# PRECISION_CLOCK_1.net
KiCad netlist of a schematic drawn in EAGLE
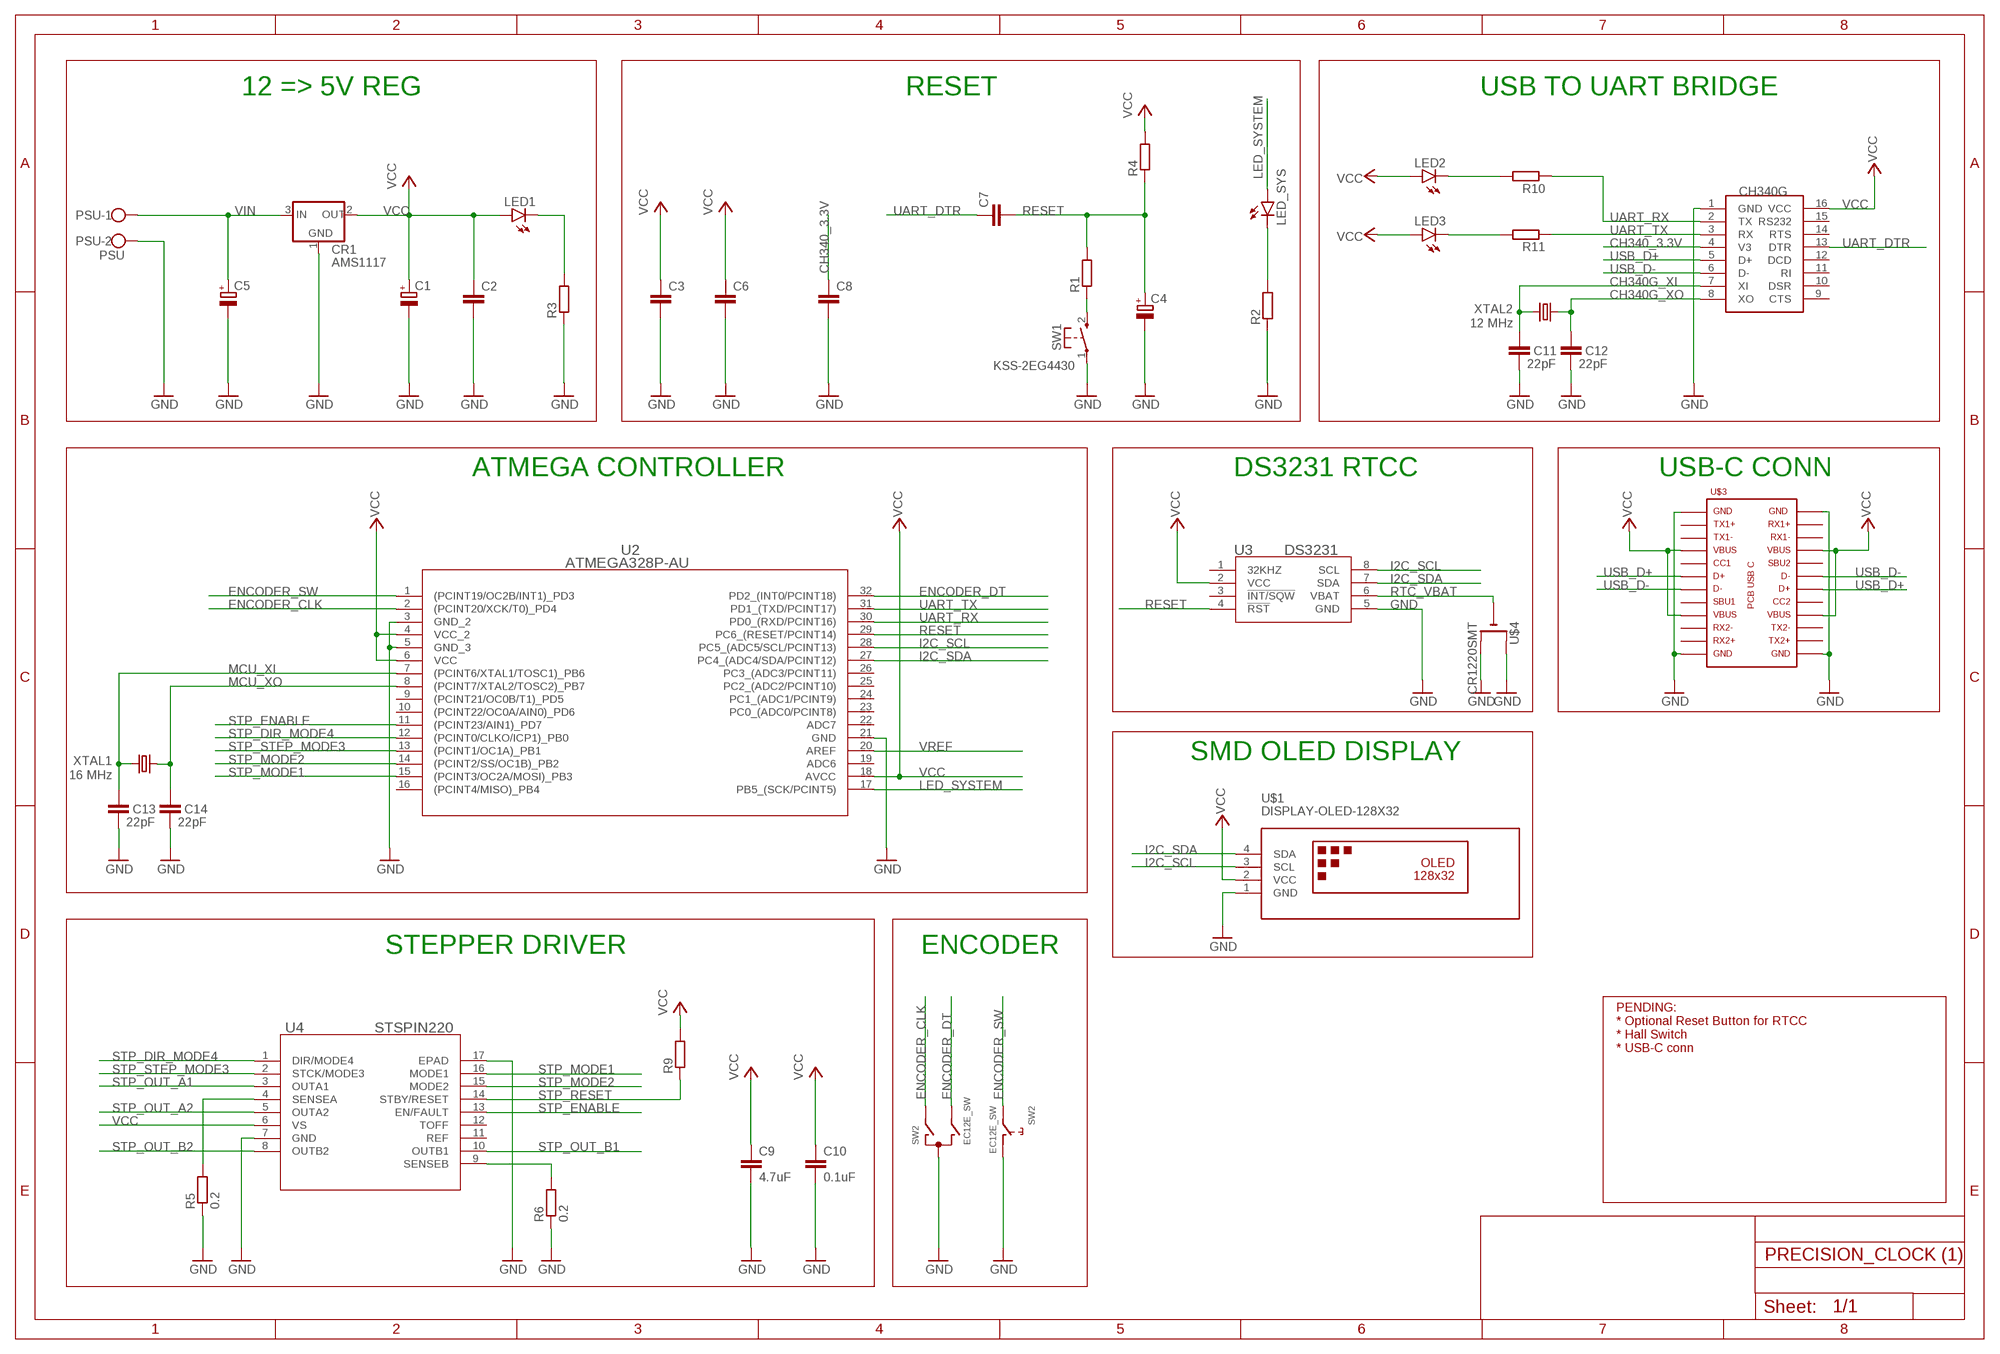
[diagram p0: schematic, sheet 1]

(export (version "E")
  (design (tool "Eeschema 10.0.6"))
  (components
    (comp (ref "C1")
      (value "CPOL-EU153CLV-0505")
      (footprint "eagle-import:153CLV-0505")
      (libsource (lib "eagle-import") (part "CPOL-EU153CLV-0505"))
    )
    (comp (ref "C2")
      (value "C-EUC0805")
      (footprint "eagle-import:C0805")
      (libsource (lib "eagle-import") (part "C-EUC0805"))
    )
    (comp (ref "C3")
      (value "C-EUC0805")
      (footprint "eagle-import:C0805")
      (libsource (lib "eagle-import") (part "C-EUC0805"))
    )
    (comp (ref "C4")
      (value "CPOL-EU153CLV-0505")
      (footprint "eagle-import:153CLV-0505")
      (libsource (lib "eagle-import") (part "CPOL-EU153CLV-0505"))
    )
    (comp (ref "C5")
      (value "CPOL-EU153CLV-0505")
      (footprint "eagle-import:153CLV-0505")
      (libsource (lib "eagle-import") (part "CPOL-EU153CLV-0505"))
    )
    (comp (ref "C6")
      (value "C-EUC0805")
      (footprint "eagle-import:C0805")
      (libsource (lib "eagle-import") (part "C-EUC0805"))
    )
    (comp (ref "C7")
      (value "C-EUC0805")
      (footprint "eagle-import:C0805")
      (libsource (lib "eagle-import") (part "C-EUC0805"))
    )
    (comp (ref "C8")
      (value "C-EUC0805")
      (footprint "eagle-import:C0805")
      (libsource (lib "eagle-import") (part "C-EUC0805"))
    )
    (comp (ref "C9")
      (value "4.7uF")
      (footprint "eagle-import:C0805")
      (libsource (lib "eagle-import") (part "C-EUC0805"))
    )
    (comp (ref "C10")
      (value "0.1uF")
      (footprint "eagle-import:C0805")
      (libsource (lib "eagle-import") (part "C-EUC0805"))
    )
    (comp (ref "C11")
      (value "22pF")
      (footprint "eagle-import:C0805")
      (libsource (lib "eagle-import") (part "C-EUC0805"))
    )
    (comp (ref "C12")
      (value "22pF")
      (footprint "eagle-import:C0805")
      (libsource (lib "eagle-import") (part "C-EUC0805"))
    )
    (comp (ref "C13")
      (value "22pF")
      (footprint "eagle-import:C0805")
      (libsource (lib "eagle-import") (part "C-EUC0805"))
    )
    (comp (ref "C14")
      (value "22pF")
      (footprint "eagle-import:C0805")
      (libsource (lib "eagle-import") (part "C-EUC0805"))
    )
    (comp (ref "CR1")
      (value "AMS1117")
      (footprint "eagle-import:SOT223")
      (libsource (lib "eagle-import") (part "AMS1117"))
    )
    (comp (ref "LED1")
      (value "LEDSML0805")
      (footprint "eagle-import:SML0805")
      (libsource (lib "eagle-import") (part "LEDSML0805"))
    )
    (comp (ref "LED2")
      (value "LEDSML0805")
      (footprint "eagle-import:SML0805")
      (libsource (lib "eagle-import") (part "LEDSML0805"))
    )
    (comp (ref "LED3")
      (value "LEDSML0805")
      (footprint "eagle-import:SML0805")
      (libsource (lib "eagle-import") (part "LEDSML0805"))
    )
    (comp (ref "LED_SYS")
      (value "LEDSML0805")
      (footprint "eagle-import:SML0805")
      (libsource (lib "eagle-import") (part "LEDSML0805"))
    )
    (comp (ref "PSU")
      (value "PSU")
      (footprint "eagle-import:W237-102")
      (fields (field (name "MPN") "237-102"))
      (libsource (lib "eagle-import") (part "W237-102"))
    )
    (comp (ref "R1")
      (value "R-EU_R0805")
      (footprint "eagle-import:R0805")
      (libsource (lib "eagle-import") (part "R-EU_R0805"))
    )
    (comp (ref "R2")
      (value "R-EU_R0805")
      (footprint "eagle-import:R0805")
      (libsource (lib "eagle-import") (part "R-EU_R0805"))
    )
    (comp (ref "R3")
      (value "R-EU_R0805")
      (footprint "eagle-import:R0805")
      (libsource (lib "eagle-import") (part "R-EU_R0805"))
    )
    (comp (ref "R4")
      (value "R-EU_R0805")
      (footprint "eagle-import:R0805")
      (libsource (lib "eagle-import") (part "R-EU_R0805"))
    )
    (comp (ref "R5")
      (value "0.2")
      (footprint "eagle-import:R0805")
      (libsource (lib "eagle-import") (part "R-EU_R0805"))
    )
    (comp (ref "R6")
      (value "0.2")
      (footprint "eagle-import:R0805")
      (libsource (lib "eagle-import") (part "R-EU_R0805"))
    )
    (comp (ref "R9")
      (value "R-EU_R0805")
      (footprint "eagle-import:R0805")
      (libsource (lib "eagle-import") (part "R-EU_R0805"))
    )
    (comp (ref "R10")
      (value "R-EU_R0805")
      (footprint "eagle-import:R0805")
      (libsource (lib "eagle-import") (part "R-EU_R0805"))
    )
    (comp (ref "R11")
      (value "R-EU_R0805")
      (footprint "eagle-import:R0805")
      (libsource (lib "eagle-import") (part "R-EU_R0805"))
    )
    (comp (ref "SW1")
      (value "KSS-2EG4430")
      (footprint "eagle-import:KSS-2EG4430")
      (libsource (lib "eagle-import") (part "KSS-2EG4430"))
    )
    (comp (ref "SW2")
      (value "EC12E_SW")
      (footprint "eagle-import:ALPS_EC12E_SW")
      (fields (field (name "MPN") "EC12E2424407"))
      (libsource (lib "eagle-import") (part "EC12E_SW"))
    )
    (comp (ref "U$1")
      (value "DISPLAY-OLED-128X32")
      (footprint "eagle-import:DISPLAY-OLED-128X32")
      (libsource (lib "eagle-import") (part "DISPLAY-OLED-128X32"))
    )
    (comp (ref "U$2")
      (value "CH340G")
      (footprint "eagle-import:SOIC16")
      (libsource (lib "eagle-import") (part "CH340G"))
    )
    (comp (ref "U$3")
      (value "PCB_USB_CDS_2")
      (footprint "eagle-import:USB_TYPE_C_DS_2")
      (libsource (lib "eagle-import") (part "PCB_USB_CDS_2"))
    )
    (comp (ref "U$4")
      (value "CR1220SMT")
      (footprint "eagle-import:CR1220-SMD")
      (fields (field (name "MF") "FDK America, Inc., a member of Fujitsu Group") (field (name "MP") "CR1220"))
      (libsource (lib "eagle-import") (part "CR1220SMT"))
    )
    (comp (ref "U2")
      (value "ATMEGA328P-AU")
      (footprint "eagle-import:32A_ATM")
      (libsource (lib "eagle-import") (part "ATMEGA328P-AU"))
    )
    (comp (ref "U3")
      (value "DS3231")
      (footprint "eagle-import:21-0041B_8_MXM")
      (fields (field (name "MANUFACTURER_PART_NUMBER") "DS3231MZ/V+T"))
      (libsource (lib "eagle-import") (part "DS3231"))
    )
    (comp (ref "U4")
      (value "STSPIN220")
      (footprint "eagle-import:VFQFPN-16_STM")
      (fields (field (name "COPYRIGHT") "Copyright (C) 2018 Accelerated Designs. All rights reserved"))
      (libsource (lib "eagle-import") (part "STSPIN220"))
    )
    (comp (ref "XTAL1")
      (value "16 MHz")
      (footprint "eagle-import:SM49")
      (libsource (lib "eagle-import") (part "CRYSTALSM49"))
    )
    (comp (ref "XTAL2")
      (value "12 MHz")
      (footprint "eagle-import:SM49")
      (libsource (lib "eagle-import") (part "CRYSTALSM49"))
    )
  )
  (nets
    (net (code "1") (name "/CH340G_XI") (class "Default")
      (node (ref "C11") (pin "1") (pinfunction "1_1") (pintype "passive"))
      (node (ref "U$2") (pin "7") (pinfunction "XI_7") (pintype "bidirectional"))
      (node (ref "XTAL2") (pin "2") (pinfunction "2_2") (pintype "passive"))
    )
    (net (code "2") (name "/CH340G_XO") (class "Default")
      (node (ref "C12") (pin "1") (pinfunction "1_1") (pintype "passive"))
      (node (ref "U$2") (pin "8") (pinfunction "XO_8") (pintype "bidirectional"))
      (node (ref "XTAL2") (pin "1") (pinfunction "1_1") (pintype "passive"))
    )
    (net (code "3") (name "/CH340_3.3V") (class "Default")
      (node (ref "C8") (pin "1") (pinfunction "1_1") (pintype "passive"))
      (node (ref "U$2") (pin "4") (pinfunction "V3_4") (pintype "bidirectional"))
    )
    (net (code "4") (name "/ENCODER_CLK") (class "Default")
      (node (ref "SW2") (pin "A") (pinfunction "A_A") (pintype "passive"))
      (node (ref "U2") (pin "2") (pinfunction "(PCINT20/XCK/T0)_PD4_2") (pintype "bidirectional"))
    )
    (net (code "5") (name "/ENCODER_DT") (class "Default")
      (node (ref "SW2") (pin "B") (pinfunction "B_B") (pintype "passive"))
      (node (ref "U2") (pin "32") (pinfunction "PD2_(INT0/PCINT18)_32") (pintype "bidirectional"))
    )
    (net (code "6") (name "/ENCODER_SW") (class "Default")
      (node (ref "SW2") (pin "E") (pinfunction "2_E") (pintype "passive"))
      (node (ref "U2") (pin "1") (pinfunction "(PCINT19/OC2B/INT1)_PD3_1") (pintype "bidirectional"))
    )
    (net (code "7") (name "/I2C_SCL") (class "Default")
      (node (ref "U$1") (pin "3") (pinfunction "SCL_3") (pintype "bidirectional"))
      (node (ref "U2") (pin "28") (pinfunction "PC5_(ADC5/SCL/PCINT13)_28") (pintype "bidirectional"))
      (node (ref "U3") (pin "8") (pinfunction "SCL_8") (pintype "passive"))
    )
    (net (code "8") (name "/I2C_SDA") (class "Default")
      (node (ref "U$1") (pin "4") (pinfunction "SDA_4") (pintype "bidirectional"))
      (node (ref "U2") (pin "27") (pinfunction "PC4_(ADC4/SDA/PCINT12)_27") (pintype "bidirectional"))
      (node (ref "U3") (pin "7") (pinfunction "SDA_7") (pintype "passive"))
    )
    (net (code "9") (name "/LED_SYSTEM") (class "Default")
      (node (ref "LED_SYS") (pin "A") (pinfunction "A_A") (pintype "passive"))
      (node (ref "U2") (pin "17") (pinfunction "PB5_(SCK/PCINT5)_17") (pintype "bidirectional"))
    )
    (net (code "10") (name "/MCU_XI") (class "Default")
      (node (ref "C13") (pin "1") (pinfunction "1_1") (pintype "passive"))
      (node (ref "U2") (pin "7") (pinfunction "(PCINT6/XTAL1/TOSC1)_PB6_7") (pintype "bidirectional"))
      (node (ref "XTAL1") (pin "2") (pinfunction "2_2") (pintype "passive"))
    )
    (net (code "11") (name "/MCU_XO") (class "Default")
      (node (ref "C14") (pin "1") (pinfunction "1_1") (pintype "passive"))
      (node (ref "U2") (pin "8") (pinfunction "(PCINT7/XTAL2/TOSC2)_PB7_8") (pintype "bidirectional"))
      (node (ref "XTAL1") (pin "1") (pinfunction "1_1") (pintype "passive"))
    )
    (net (code "12") (name "/RESET") (class "Default")
      (node (ref "C4") (pin "+") (pinfunction "+_+") (pintype "passive"))
      (node (ref "C7") (pin "2") (pinfunction "2_2") (pintype "passive"))
      (node (ref "R1") (pin "2") (pinfunction "2_2") (pintype "passive"))
      (node (ref "R4") (pin "1") (pinfunction "1_1") (pintype "passive"))
      (node (ref "U2") (pin "29") (pinfunction "PC6_(RESET/PCINT14)_29") (pintype "bidirectional"))
      (node (ref "U3") (pin "4") (pinfunction "~{RST}_4") (pintype "passive"))
    )
    (net (code "13") (name "/RTC_VBAT") (class "Default")
      (node (ref "U$4") (pin "-") (pinfunction "-_-") (pintype "passive"))
      (node (ref "U3") (pin "6") (pinfunction "VBAT_6") (pintype "power_in"))
    )
    (net (code "14") (name "/STP_DIR_MODE4") (class "Default")
      (node (ref "U2") (pin "12") (pinfunction "(PCINT0/CLKO/ICP1)_PB0_12") (pintype "bidirectional"))
      (node (ref "U4") (pin "1") (pinfunction "DIR/MODE4_1") (pintype "input"))
    )
    (net (code "15") (name "/STP_ENABLE") (class "Default")
      (node (ref "U2") (pin "11") (pinfunction "(PCINT23/AIN1)_PD7_11") (pintype "bidirectional"))
      (node (ref "U4") (pin "13") (pinfunction "EN/FAULT_13") (pintype "bidirectional"))
    )
    (net (code "16") (name "/STP_MODE1") (class "Default")
      (node (ref "U2") (pin "15") (pinfunction "(PCINT3/OC2A/MOSI)_PB3_15") (pintype "bidirectional"))
      (node (ref "U4") (pin "16") (pinfunction "MODE1_16") (pintype "input"))
    )
    (net (code "17") (name "/STP_MODE2") (class "Default")
      (node (ref "U2") (pin "14") (pinfunction "(PCINT2/SS/OC1B)_PB2_14") (pintype "bidirectional"))
      (node (ref "U4") (pin "15") (pinfunction "MODE2_15") (pintype "input"))
    )
    (net (code "18") (name "/STP_OUT_A1") (class "Default")
      (node (ref "U4") (pin "3") (pinfunction "OUTA1_3") (pintype "output"))
    )
    (net (code "19") (name "/STP_OUT_A2") (class "Default")
      (node (ref "U4") (pin "5") (pinfunction "OUTA2_5") (pintype "output"))
    )
    (net (code "20") (name "/STP_OUT_B1") (class "Default")
      (node (ref "U4") (pin "10") (pinfunction "OUTB1_10") (pintype "output"))
    )
    (net (code "21") (name "/STP_OUT_B2") (class "Default")
      (node (ref "U4") (pin "8") (pinfunction "OUTB2_8") (pintype "output"))
    )
    (net (code "22") (name "/STP_RESET") (class "Default")
      (node (ref "R9") (pin "1") (pinfunction "1_1") (pintype "passive"))
      (node (ref "U4") (pin "14") (pinfunction "STBY/RESET_14") (pintype "input"))
    )
    (net (code "23") (name "/STP_STEP_MODE3") (class "Default")
      (node (ref "U2") (pin "13") (pinfunction "(PCINT1/OC1A)_PB1_13") (pintype "bidirectional"))
      (node (ref "U4") (pin "2") (pinfunction "STCK/MODE3_2") (pintype "input"))
    )
    (net (code "24") (name "/UART_DTR") (class "Default")
      (node (ref "C7") (pin "1") (pinfunction "1_1") (pintype "passive"))
      (node (ref "U$2") (pin "13") (pinfunction "DTR_13") (pintype "bidirectional"))
    )
    (net (code "25") (name "/UART_RX") (class "Default")
      (node (ref "R10") (pin "1") (pinfunction "1_1") (pintype "passive"))
      (node (ref "U$2") (pin "2") (pinfunction "TX_2") (pintype "bidirectional"))
      (node (ref "U2") (pin "30") (pinfunction "PD0_(RXD/PCINT16)_30") (pintype "bidirectional"))
    )
    (net (code "26") (name "/UART_TX") (class "Default")
      (node (ref "R11") (pin "1") (pinfunction "1_1") (pintype "passive"))
      (node (ref "U$2") (pin "3") (pinfunction "RX_3") (pintype "bidirectional"))
      (node (ref "U2") (pin "31") (pinfunction "PD1_(TXD/PCINT17)_31") (pintype "bidirectional"))
    )
    (net (code "27") (name "/USB_D+") (class "Default")
      (node (ref "U$2") (pin "5") (pinfunction "D+_5") (pintype "bidirectional"))
      (node (ref "U$3") (pin "A6") (pinfunction "A6_A6") (pintype "bidirectional"))
      (node (ref "U$3") (pin "B6") (pinfunction "B6_B6") (pintype "bidirectional"))
    )
    (net (code "28") (name "/USB_D-") (class "Default")
      (node (ref "U$2") (pin "6") (pinfunction "D-_6") (pintype "bidirectional"))
      (node (ref "U$3") (pin "A7") (pinfunction "A7_A7") (pintype "bidirectional"))
      (node (ref "U$3") (pin "B7") (pinfunction "B7_B7") (pintype "bidirectional"))
    )
    (net (code "29") (name "/VIN") (class "Default")
      (node (ref "C5") (pin "+") (pinfunction "+_+") (pintype "passive"))
      (node (ref "CR1") (pin "3") (pinfunction "IN_3") (pintype "input"))
      (node (ref "PSU") (pin "1") (pinfunction "KL_1") (pintype "passive"))
    )
    (net (code "30") (name "/VREF") (class "Default")
      (node (ref "U2") (pin "20") (pinfunction "AREF_20") (pintype "passive"))
    )
    (net (code "31") (name "GND") (class "Default")
      (node (ref "C1") (pin "-") (pinfunction "-_-") (pintype "passive"))
      (node (ref "C10") (pin "2") (pinfunction "2_2") (pintype "passive"))
      (node (ref "C11") (pin "2") (pinfunction "2_2") (pintype "passive"))
      (node (ref "C12") (pin "2") (pinfunction "2_2") (pintype "passive"))
      (node (ref "C13") (pin "2") (pinfunction "2_2") (pintype "passive"))
      (node (ref "C14") (pin "2") (pinfunction "2_2") (pintype "passive"))
      (node (ref "C2") (pin "2") (pinfunction "2_2") (pintype "passive"))
      (node (ref "C3") (pin "2") (pinfunction "2_2") (pintype "passive"))
      (node (ref "C4") (pin "-") (pinfunction "-_-") (pintype "passive"))
      (node (ref "C5") (pin "-") (pinfunction "-_-") (pintype "passive"))
      (node (ref "C6") (pin "2") (pinfunction "2_2") (pintype "passive"))
      (node (ref "C8") (pin "2") (pinfunction "2_2") (pintype "passive"))
      (node (ref "C9") (pin "2") (pinfunction "2_2") (pintype "passive"))
      (node (ref "CR1") (pin "1") (pinfunction "GROUND_1") (pintype "passive"))
      (node (ref "PSU") (pin "2") (pinfunction "KL_2") (pintype "passive"))
      (node (ref "R2") (pin "1") (pinfunction "1_1") (pintype "passive"))
      (node (ref "R3") (pin "1") (pinfunction "1_1") (pintype "passive"))
      (node (ref "R5") (pin "1") (pinfunction "1_1") (pintype "passive"))
      (node (ref "R6") (pin "1") (pinfunction "1_1") (pintype "passive"))
      (node (ref "SW1") (pin "1") (pinfunction "P_1") (pintype "passive"))
      (node (ref "SW2") (pin "C") (pinfunction "C_C") (pintype "passive"))
      (node (ref "SW2") (pin "D") (pinfunction "1_D") (pintype "passive"))
      (node (ref "U$1") (pin "1") (pinfunction "GND_1") (pintype "power_in"))
      (node (ref "U$2") (pin "1") (pinfunction "GND_1") (pintype "bidirectional"))
      (node (ref "U$3") (pin "A1") (pinfunction "A1_A1") (pintype "bidirectional"))
      (node (ref "U$3") (pin "A12") (pinfunction "A12_A12") (pintype "bidirectional"))
      (node (ref "U$3") (pin "B1") (pinfunction "B1_B1") (pintype "bidirectional"))
      (node (ref "U$3") (pin "B12") (pinfunction "B12_B12") (pintype "bidirectional"))
      (node (ref "U$4") (pin "+$1") (pinfunction "+_+$1") (pintype "passive"))
      (node (ref "U$4") (pin "+$2") (pinfunction "+1_+$2") (pintype "passive"))
      (node (ref "U2") (pin "21") (pinfunction "GND_21") (pintype "power_in"))
      (node (ref "U2") (pin "3") (pinfunction "GND_2_3") (pintype "power_in"))
      (node (ref "U2") (pin "5") (pinfunction "GND_3_5") (pintype "power_in"))
      (node (ref "U3") (pin "5") (pinfunction "GND_5") (pintype "power_in"))
      (node (ref "U4") (pin "17") (pinfunction "EPAD_17") (pintype "passive"))
      (node (ref "U4") (pin "7") (pinfunction "GND_7") (pintype "power_in"))
    )
    (net (code "32") (name "Net-(LED1-PadC)") (class "Default")
      (node (ref "LED1") (pin "C") (pinfunction "C_C") (pintype "passive"))
      (node (ref "R3") (pin "2") (pinfunction "2_2") (pintype "passive"))
    )
    (net (code "33") (name "Net-(LED2-PadC)") (class "Default")
      (node (ref "LED2") (pin "C") (pinfunction "C_C") (pintype "passive"))
      (node (ref "R10") (pin "2") (pinfunction "2_2") (pintype "passive"))
    )
    (net (code "34") (name "Net-(LED3-PadC)") (class "Default")
      (node (ref "LED3") (pin "C") (pinfunction "C_C") (pintype "passive"))
      (node (ref "R11") (pin "2") (pinfunction "2_2") (pintype "passive"))
    )
    (net (code "35") (name "Net-(LED_SYS-PadC)") (class "Default")
      (node (ref "LED_SYS") (pin "C") (pinfunction "C_C") (pintype "passive"))
      (node (ref "R2") (pin "2") (pinfunction "2_2") (pintype "passive"))
    )
    (net (code "36") (name "Net-(SW1-S)") (class "Default")
      (node (ref "R1") (pin "1") (pinfunction "1_1") (pintype "passive"))
      (node (ref "SW1") (pin "2") (pinfunction "S_2") (pintype "passive"))
    )
    (net (code "37") (name "Net-(U4-SENSEA)") (class "Default")
      (node (ref "R5") (pin "2") (pinfunction "2_2") (pintype "passive"))
      (node (ref "U4") (pin "4") (pinfunction "SENSEA_4") (pintype "output"))
    )
    (net (code "38") (name "Net-(U4-SENSEB)") (class "Default")
      (node (ref "R6") (pin "2") (pinfunction "2_2") (pintype "passive"))
      (node (ref "U4") (pin "9") (pinfunction "SENSEB_9") (pintype "output"))
    )
    (net (code "39") (name "VCC") (class "Default")
      (node (ref "C1") (pin "+") (pinfunction "+_+") (pintype "passive"))
      (node (ref "C10") (pin "1") (pinfunction "1_1") (pintype "passive"))
      (node (ref "C2") (pin "1") (pinfunction "1_1") (pintype "passive"))
      (node (ref "C3") (pin "1") (pinfunction "1_1") (pintype "passive"))
      (node (ref "C6") (pin "1") (pinfunction "1_1") (pintype "passive"))
      (node (ref "C9") (pin "1") (pinfunction "1_1") (pintype "passive"))
      (node (ref "CR1") (pin "2") (pinfunction "OUT_2") (pintype "output"))
      (node (ref "LED1") (pin "A") (pinfunction "A_A") (pintype "passive"))
      (node (ref "LED2") (pin "A") (pinfunction "A_A") (pintype "passive"))
      (node (ref "LED3") (pin "A") (pinfunction "A_A") (pintype "passive"))
      (node (ref "R4") (pin "2") (pinfunction "2_2") (pintype "passive"))
      (node (ref "R9") (pin "2") (pinfunction "2_2") (pintype "passive"))
      (node (ref "U$1") (pin "2") (pinfunction "VCC_2") (pintype "power_in"))
      (node (ref "U$2") (pin "16") (pinfunction "VCC_16") (pintype "bidirectional"))
      (node (ref "U$3") (pin "A4") (pinfunction "A4_A4") (pintype "bidirectional"))
      (node (ref "U$3") (pin "A9") (pinfunction "A9_A9") (pintype "bidirectional"))
      (node (ref "U$3") (pin "B4") (pinfunction "B4_B4") (pintype "bidirectional"))
      (node (ref "U$3") (pin "B9") (pinfunction "B9_B9") (pintype "bidirectional"))
      (node (ref "U2") (pin "18") (pinfunction "AVCC_18") (pintype "power_in"))
      (node (ref "U2") (pin "4") (pinfunction "VCC_2_4") (pintype "power_in"))
      (node (ref "U2") (pin "6") (pinfunction "VCC_6") (pintype "power_in"))
      (node (ref "U3") (pin "2") (pinfunction "VCC_2") (pintype "power_in"))
      (node (ref "U4") (pin "6") (pinfunction "VS_6") (pintype "power_in"))
    )
    (net (code "40") (name "unconnected-(U$2-CTS-Pad9)") (class "Default")
      (node (ref "U$2") (pin "9") (pinfunction "CTS_9") (pintype "bidirectional"))
    )
    (net (code "41") (name "unconnected-(U$2-DCD-Pad12)") (class "Default")
      (node (ref "U$2") (pin "12") (pinfunction "DCD_12") (pintype "bidirectional"))
    )
    (net (code "42") (name "unconnected-(U$2-DSR-Pad10)") (class "Default")
      (node (ref "U$2") (pin "10") (pinfunction "DSR_10") (pintype "bidirectional"))
    )
    (net (code "43") (name "unconnected-(U$2-RI-Pad11)") (class "Default")
      (node (ref "U$2") (pin "11") (pinfunction "RI_11") (pintype "bidirectional"))
    )
    (net (code "44") (name "unconnected-(U$2-RS232-Pad15)") (class "Default")
      (node (ref "U$2") (pin "15") (pinfunction "RS232_15") (pintype "bidirectional"))
    )
    (net (code "45") (name "unconnected-(U$2-RTS-Pad14)") (class "Default")
      (node (ref "U$2") (pin "14") (pinfunction "RTS_14") (pintype "bidirectional"))
    )
    (net (code "46") (name "unconnected-(U$3-PadA2)") (class "Default")
      (node (ref "U$3") (pin "A2") (pinfunction "A2_A2") (pintype "bidirectional"))
    )
    (net (code "47") (name "unconnected-(U$3-PadA3)") (class "Default")
      (node (ref "U$3") (pin "A3") (pinfunction "A3_A3") (pintype "bidirectional"))
    )
    (net (code "48") (name "unconnected-(U$3-PadA5)") (class "Default")
      (node (ref "U$3") (pin "A5") (pinfunction "A5_A5") (pintype "bidirectional"))
    )
    (net (code "49") (name "unconnected-(U$3-PadA8)") (class "Default")
      (node (ref "U$3") (pin "A8") (pinfunction "A8_A8") (pintype "bidirectional"))
    )
    (net (code "50") (name "unconnected-(U$3-PadA10)") (class "Default")
      (node (ref "U$3") (pin "A10") (pinfunction "A10_A10") (pintype "bidirectional"))
    )
    (net (code "51") (name "unconnected-(U$3-PadA11)") (class "Default")
      (node (ref "U$3") (pin "A11") (pinfunction "A11_A11") (pintype "bidirectional"))
    )
    (net (code "52") (name "unconnected-(U$3-PadB2)") (class "Default")
      (node (ref "U$3") (pin "B2") (pinfunction "B2_B2") (pintype "bidirectional"))
    )
    (net (code "53") (name "unconnected-(U$3-PadB3)") (class "Default")
      (node (ref "U$3") (pin "B3") (pinfunction "B3_B3") (pintype "bidirectional"))
    )
    (net (code "54") (name "unconnected-(U$3-PadB5)") (class "Default")
      (node (ref "U$3") (pin "B5") (pinfunction "B5_B5") (pintype "bidirectional"))
    )
    (net (code "55") (name "unconnected-(U$3-PadB8)") (class "Default")
      (node (ref "U$3") (pin "B8") (pinfunction "B8_B8") (pintype "bidirectional"))
    )
    (net (code "56") (name "unconnected-(U$3-PadB10)") (class "Default")
      (node (ref "U$3") (pin "B10") (pinfunction "B10_B10") (pintype "bidirectional"))
    )
    (net (code "57") (name "unconnected-(U$3-PadB11)") (class "Default")
      (node (ref "U$3") (pin "B11") (pinfunction "B11_B11") (pintype "bidirectional"))
    )
    (net (code "58") (name "unconnected-(U2-(PCINT4{slash}MISO)_PB4-Pad16)") (class "Default")
      (node (ref "U2") (pin "16") (pinfunction "(PCINT4/MISO)_PB4_16") (pintype "bidirectional"))
    )
    (net (code "59") (name "unconnected-(U2-(PCINT21{slash}OC0B{slash}T1)_PD5-Pad9)") (class "Default")
      (node (ref "U2") (pin "9") (pinfunction "(PCINT21/OC0B/T1)_PD5_9") (pintype "bidirectional"))
    )
    (net (code "60") (name "unconnected-(U2-(PCINT22{slash}OC0A{slash}AIN0)_PD6-Pad10)") (class "Default")
      (node (ref "U2") (pin "10") (pinfunction "(PCINT22/OC0A/AIN0)_PD6_10") (pintype "bidirectional"))
    )
    (net (code "61") (name "unconnected-(U2-ADC6-Pad19)") (class "Default")
      (node (ref "U2") (pin "19") (pinfunction "ADC6_19") (pintype "input"))
    )
    (net (code "62") (name "unconnected-(U2-ADC7-Pad22)") (class "Default")
      (node (ref "U2") (pin "22") (pinfunction "ADC7_22") (pintype "input"))
    )
    (net (code "63") (name "unconnected-(U2-PC0_(ADC0{slash}PCINT8)-Pad23)") (class "Default")
      (node (ref "U2") (pin "23") (pinfunction "PC0_(ADC0/PCINT8)_23") (pintype "bidirectional"))
    )
    (net (code "64") (name "unconnected-(U2-PC1_(ADC1{slash}PCINT9)-Pad24)") (class "Default")
      (node (ref "U2") (pin "24") (pinfunction "PC1_(ADC1/PCINT9)_24") (pintype "bidirectional"))
    )
    (net (code "65") (name "unconnected-(U2-PC2_(ADC2{slash}PCINT10)-Pad25)") (class "Default")
      (node (ref "U2") (pin "25") (pinfunction "PC2_(ADC2/PCINT10)_25") (pintype "bidirectional"))
    )
    (net (code "66") (name "unconnected-(U2-PC3_(ADC3{slash}PCINT11)-Pad26)") (class "Default")
      (node (ref "U2") (pin "26") (pinfunction "PC3_(ADC3/PCINT11)_26") (pintype "bidirectional"))
    )
    (net (code "67") (name "unconnected-(U3-32KHZ-Pad1)") (class "Default")
      (node (ref "U3") (pin "1") (pinfunction "32KHZ_1") (pintype "passive"))
    )
    (net (code "68") (name "unconnected-(U3-~{INT{slash}SQW}-Pad3)") (class "Default")
      (node (ref "U3") (pin "3") (pinfunction "~{INT/SQW}_3") (pintype "passive"))
    )
    (net (code "69") (name "unconnected-(U4-REF-Pad11)") (class "Default")
      (node (ref "U4") (pin "11") (pinfunction "REF_11") (pintype "input"))
    )
    (net (code "70") (name "unconnected-(U4-TOFF-Pad12)") (class "Default")
      (node (ref "U4") (pin "12") (pinfunction "TOFF_12") (pintype "input"))
    )
  )
)
